# ZX_Distance_and_Gesture_Sensor_PTH.net
KiCad netlist of a schematic drawn in EAGLE
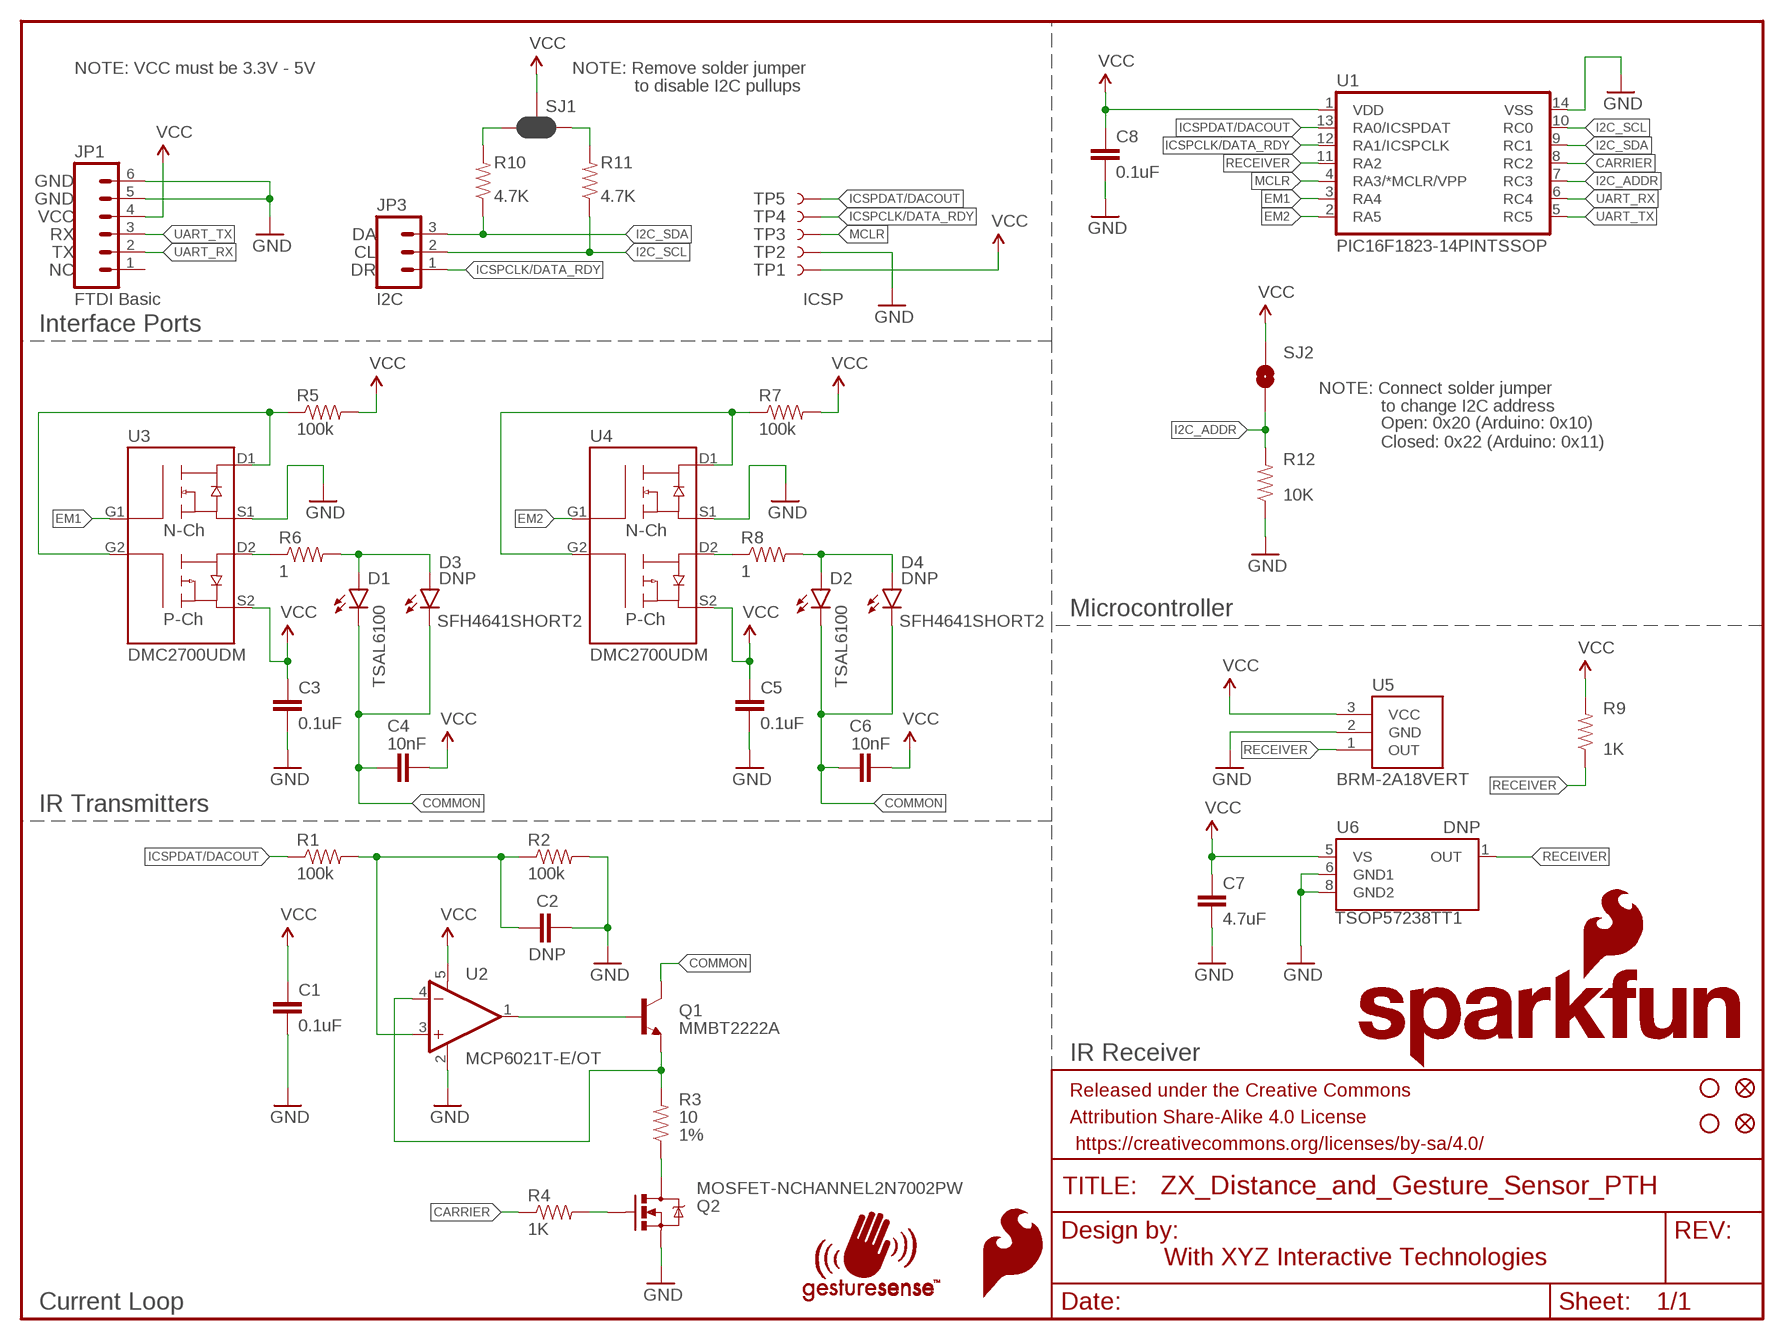
[diagram p0: schematic, sheet 1]

(export (version "E")
  (design (tool "Eeschema 10.0.6"))
  (components
    (comp (ref "C1")
      (value "0.1uF")
      (footprint "eagle-import:0603-CAP")
      (libsource (lib "eagle-import") (part "0.1UF-25V(+80/-20%)(0603)"))
    )
    (comp (ref "C2")
      (value "DNP")
      (footprint "eagle-import:0603-CAP")
      (libsource (lib "eagle-import") (part "CAP0603-CAP"))
    )
    (comp (ref "C3")
      (value "0.1uF")
      (footprint "eagle-import:0603-CAP")
      (libsource (lib "eagle-import") (part "0.1UF-25V(+80/-20%)(0603)"))
    )
    (comp (ref "C4")
      (value "10nF")
      (footprint "eagle-import:0603-CAP")
      (libsource (lib "eagle-import") (part "10NF/10000PF-50V-10%(0603)"))
    )
    (comp (ref "C5")
      (value "0.1uF")
      (footprint "eagle-import:0603-CAP")
      (libsource (lib "eagle-import") (part "0.1UF-25V(+80/-20%)(0603)"))
    )
    (comp (ref "C6")
      (value "10nF")
      (footprint "eagle-import:0603-CAP")
      (libsource (lib "eagle-import") (part "10NF/10000PF-50V-10%(0603)"))
    )
    (comp (ref "C7")
      (value "4.7uF")
      (footprint "eagle-import:0603-CAP")
      (libsource (lib "eagle-import") (part "4.7UF-6.3V-10%(0603)0603"))
    )
    (comp (ref "C8")
      (value "0.1uF")
      (footprint "eagle-import:0603-CAP")
      (libsource (lib "eagle-import") (part "0.1UF-25V(+80/-20%)(0603)"))
    )
    (comp (ref "D1")
      (value "LED-IR-THRUTSAL6100")
      (footprint "eagle-import:LED5MM")
      (fields (field (name "VARIANT") "TSAL6100"))
      (libsource (lib "eagle-import") (part "LED-IR-THRUTSAL6100"))
    )
    (comp (ref "D2")
      (value "LED-IR-THRUTSAL6100")
      (footprint "eagle-import:LED5MM")
      (fields (field (name "VARIANT") "TSAL6100"))
      (libsource (lib "eagle-import") (part "LED-IR-THRUTSAL6100"))
    )
    (comp (ref "D3")
      (value "SFH4641SHORT2")
      (footprint "eagle-import:SFH4641-SHORT2")
      (libsource (lib "eagle-import") (part "SFH4641SHORT2"))
    )
    (comp (ref "D4")
      (value "SFH4641SHORT2")
      (footprint "eagle-import:SFH4641-SHORT2")
      (libsource (lib "eagle-import") (part "SFH4641SHORT2"))
    )
    (comp (ref "FID1")
      (value "FIDUCIAL1X2")
      (footprint "eagle-import:FIDUCIAL-1X2")
      (libsource (lib "eagle-import") (part "FIDUCIAL1X2"))
    )
    (comp (ref "FID2")
      (value "FIDUCIAL1X2")
      (footprint "eagle-import:FIDUCIAL-1X2")
      (libsource (lib "eagle-import") (part "FIDUCIAL1X2"))
    )
    (comp (ref "FRAME1")
      (value "FRAME-LETTER")
      (footprint "eagle-import:CREATIVE_COMMONS")
      (libsource (lib "eagle-import") (part "FRAME-LETTER"))
    )
    (comp (ref "JP1")
      (value "M06NO_SILK_FEMALE_PTH")
      (footprint "eagle-import:1X06_NO_SILK")
      (libsource (lib "eagle-import") (part "M06NO_SILK_FEMALE_PTH"))
    )
    (comp (ref "JP3")
      (value "M031X03_NO_SILK")
      (footprint "eagle-import:1X03_NO_SILK")
      (libsource (lib "eagle-import") (part "M031X03_NO_SILK"))
    )
    (comp (ref "LOGO1")
      (value "SFE_LOGO_FLAME.1_INCH")
      (footprint "eagle-import:SFE_LOGO_FLAME_.1")
      (libsource (lib "eagle-import") (part "SFE_LOGO_FLAME.1_INCH"))
    )
    (comp (ref "Q1")
      (value "MMBT2222A")
      (footprint "eagle-import:SOT23-3")
      (libsource (lib "eagle-import") (part "TRANSISTOR_NPNMMBT2222A"))
    )
    (comp (ref "Q2")
      (value "MOSFET-NCHANNEL2N7002PW")
      (footprint "eagle-import:SOT323")
      (libsource (lib "eagle-import") (part "MOSFET-NCHANNEL2N7002PW"))
    )
    (comp (ref "R1")
      (value "100k")
      (footprint "eagle-import:0603-RES")
      (libsource (lib "eagle-import") (part "100KOHM-1/10W-1%(0603)"))
    )
    (comp (ref "R2")
      (value "100k")
      (footprint "eagle-import:0603-RES")
      (libsource (lib "eagle-import") (part "100KOHM-1/10W-1%(0603)"))
    )
    (comp (ref "R3")
      (value "10")
      (footprint "eagle-import:0603-RES")
      (fields (field (name "TOL") "1%"))
      (libsource (lib "eagle-import") (part "10OHM-1/10W-1%(0603)SMD"))
    )
    (comp (ref "R4")
      (value "1K")
      (footprint "eagle-import:0603-RES")
      (libsource (lib "eagle-import") (part "1KOHM-1/10W-1%(0603)"))
    )
    (comp (ref "R5")
      (value "100k")
      (footprint "eagle-import:0603-RES")
      (libsource (lib "eagle-import") (part "100KOHM-1/10W-1%(0603)"))
    )
    (comp (ref "R6")
      (value "1")
      (footprint "eagle-import:0603-RES")
      (libsource (lib "eagle-import") (part "1OHM1/10W1%(0603)"))
    )
    (comp (ref "R7")
      (value "100k")
      (footprint "eagle-import:0603-RES")
      (libsource (lib "eagle-import") (part "100KOHM-1/10W-1%(0603)"))
    )
    (comp (ref "R8")
      (value "1")
      (footprint "eagle-import:0603-RES")
      (libsource (lib "eagle-import") (part "1OHM1/10W1%(0603)"))
    )
    (comp (ref "R9")
      (value "1K")
      (footprint "eagle-import:0603-RES")
      (libsource (lib "eagle-import") (part "1KOHM-1/10W-1%(0603)"))
    )
    (comp (ref "R10")
      (value "4.7K")
      (footprint "eagle-import:0603-RES")
      (libsource (lib "eagle-import") (part "4.7KOHM-1/10W-1%(0603)"))
    )
    (comp (ref "R11")
      (value "4.7K")
      (footprint "eagle-import:0603-RES")
      (libsource (lib "eagle-import") (part "4.7KOHM-1/10W-1%(0603)"))
    )
    (comp (ref "R12")
      (value "10K")
      (footprint "eagle-import:0603-RES")
      (libsource (lib "eagle-import") (part "10KOHM-1/10W-1%(0603)0603"))
    )
    (comp (ref "SJ1")
      (value "JUMPER-PAD-3-NC_BY_PASTE")
      (footprint "eagle-import:PAD-JUMPER-3-NC_BY_PASTE_YES_SILK_FULL_BOX")
      (libsource (lib "eagle-import") (part "JUMPER-PAD-3-NC_BY_PASTE"))
    )
    (comp (ref "SJ2")
      (value "JUMPER-PAD-2-NOYES_SILK")
      (footprint "eagle-import:PAD-JUMPER-2-NO_YES_SILK")
      (libsource (lib "eagle-import") (part "JUMPER-PAD-2-NOYES_SILK"))
    )
    (comp (ref "STANDOFF1")
      (value "STAND-OFF")
      (footprint "eagle-import:STAND-OFF")
      (libsource (lib "eagle-import") (part "STAND-OFF"))
    )
    (comp (ref "STANDOFF2")
      (value "STAND-OFF")
      (footprint "eagle-import:STAND-OFF")
      (libsource (lib "eagle-import") (part "STAND-OFF"))
    )
    (comp (ref "TP1")
      (value "TEST-POINT3X4")
      (footprint "eagle-import:PAD.03X.04")
      (libsource (lib "eagle-import") (part "TEST-POINT3X4"))
    )
    (comp (ref "TP2")
      (value "TEST-POINT3X4")
      (footprint "eagle-import:PAD.03X.04")
      (libsource (lib "eagle-import") (part "TEST-POINT3X4"))
    )
    (comp (ref "TP3")
      (value "TEST-POINT3X4")
      (footprint "eagle-import:PAD.03X.04")
      (libsource (lib "eagle-import") (part "TEST-POINT3X4"))
    )
    (comp (ref "TP4")
      (value "TEST-POINT3X4")
      (footprint "eagle-import:PAD.03X.04")
      (libsource (lib "eagle-import") (part "TEST-POINT3X4"))
    )
    (comp (ref "TP5")
      (value "TEST-POINT3X4")
      (footprint "eagle-import:PAD.03X.04")
      (libsource (lib "eagle-import") (part "TEST-POINT3X4"))
    )
    (comp (ref "U$5")
      (value "SFE_LOGO_NAME_FLAME.1_INCH")
      (footprint "eagle-import:SFE_LOGO_NAME_FLAME_.1")
      (libsource (lib "eagle-import") (part "SFE_LOGO_NAME_FLAME.1_INCH"))
    )
    (comp (ref "U$6")
      (value "GESTURESENSE_LOGOSTEXT")
      (footprint "eagle-import:GESTURESENSE_TEXT")
      (libsource (lib "eagle-import") (part "GESTURESENSE_LOGOSTEXT"))
    )
    (comp (ref "U1")
      (value "PIC16F1823-14PINTSSOP")
      (footprint "eagle-import:TSSOP14")
      (libsource (lib "eagle-import") (part "PIC16F1823-14PINTSSOP"))
    )
    (comp (ref "U2")
      (value "MCP6021T-E/OT")
      (footprint "eagle-import:SOT23-5")
      (libsource (lib "eagle-import") (part "MCP6021T-E/OT"))
    )
    (comp (ref "U3")
      (value "DMC2700UDM")
      (footprint "eagle-import:SOT26")
      (libsource (lib "eagle-import") (part "DMC2700UDM"))
    )
    (comp (ref "U4")
      (value "DMC2700UDM")
      (footprint "eagle-import:SOT26")
      (libsource (lib "eagle-import") (part "DMC2700UDM"))
    )
    (comp (ref "U5")
      (value "BRM-2A18VERT")
      (footprint "eagle-import:BRM-2508_VERT")
      (libsource (lib "eagle-import") (part "BRM-2A18VERT"))
    )
    (comp (ref "U6")
      (value "TSOP57238TT1")
      (footprint "eagle-import:TSOP572")
      (fields (field (name "PLACE") "DNP"))
      (libsource (lib "eagle-import") (part "TSOP57238TT1"))
    )
  )
  (nets
    (net (code "1") (name "CARRIER") (class "Default")
      (node (ref "R4") (pin "1") (pinfunction "1_1") (pintype "passive"))
      (node (ref "U1") (pin "8") (pinfunction "RC2_8") (pintype "bidirectional"))
    )
    (net (code "2") (name "COMMON") (class "Default")
      (node (ref "C4") (pin "1") (pinfunction "1_1") (pintype "passive"))
      (node (ref "C6") (pin "1") (pinfunction "1_1") (pintype "passive"))
      (node (ref "D1") (pin "K") (pinfunction "C_K") (pintype "passive"))
      (node (ref "D2") (pin "K") (pinfunction "C_K") (pintype "passive"))
      (node (ref "D3") (pin "C") (pinfunction "C_C") (pintype "passive"))
      (node (ref "D4") (pin "C") (pinfunction "C_C") (pintype "passive"))
      (node (ref "Q1") (pin "3") (pinfunction "C_3") (pintype "passive"))
    )
    (net (code "3") (name "EM1") (class "Default")
      (node (ref "U1") (pin "3") (pinfunction "RA4_3") (pintype "bidirectional"))
      (node (ref "U3") (pin "G1") (pinfunction "G1_G1") (pintype "bidirectional"))
    )
    (net (code "4") (name "EM2") (class "Default")
      (node (ref "U1") (pin "2") (pinfunction "RA5_2") (pintype "bidirectional"))
      (node (ref "U4") (pin "G1") (pinfunction "G1_G1") (pintype "bidirectional"))
    )
    (net (code "5") (name "GND") (class "Default")
      (node (ref "C1") (pin "2") (pinfunction "2_2") (pintype "passive"))
      (node (ref "C2") (pin "2") (pinfunction "2_2") (pintype "passive"))
      (node (ref "C3") (pin "2") (pinfunction "2_2") (pintype "passive"))
      (node (ref "C5") (pin "2") (pinfunction "2_2") (pintype "passive"))
      (node (ref "C7") (pin "2") (pinfunction "2_2") (pintype "passive"))
      (node (ref "C8") (pin "2") (pinfunction "2_2") (pintype "passive"))
      (node (ref "JP1") (pin "5") (pinfunction "5_5") (pintype "passive"))
      (node (ref "JP1") (pin "6") (pinfunction "6_6") (pintype "passive"))
      (node (ref "Q2") (pin "2") (pinfunction "S_2") (pintype "passive"))
      (node (ref "R12") (pin "1") (pinfunction "1_1") (pintype "passive"))
      (node (ref "R2") (pin "2") (pinfunction "2_2") (pintype "passive"))
      (node (ref "TP2") (pin "P$1") (pinfunction "1_P$1") (pintype "bidirectional"))
      (node (ref "U1") (pin "14") (pinfunction "VSS_14") (pintype "power_in"))
      (node (ref "U2") (pin "2") (pinfunction "V-_2") (pintype "power_in"))
      (node (ref "U3") (pin "S1") (pinfunction "S1_S1") (pintype "bidirectional"))
      (node (ref "U4") (pin "S1") (pinfunction "S1_S1") (pintype "bidirectional"))
      (node (ref "U5") (pin "2") (pinfunction "GND_2") (pintype "bidirectional"))
      (node (ref "U6") (pin "6") (pinfunction "GND1_6") (pintype "bidirectional"))
      (node (ref "U6") (pin "8") (pinfunction "GND2_8") (pintype "bidirectional"))
    )
    (net (code "6") (name "I2C_ADDR") (class "Default")
      (node (ref "R12") (pin "2") (pinfunction "2_2") (pintype "passive"))
      (node (ref "SJ2") (pin "1") (pinfunction "1_1") (pintype "passive"))
      (node (ref "U1") (pin "7") (pinfunction "RC3_7") (pintype "bidirectional"))
    )
    (net (code "7") (name "I2C_SCL") (class "Default")
      (node (ref "JP3") (pin "2") (pinfunction "2_2") (pintype "passive"))
      (node (ref "R11") (pin "1") (pinfunction "1_1") (pintype "passive"))
      (node (ref "U1") (pin "10") (pinfunction "RC0_10") (pintype "bidirectional"))
    )
    (net (code "8") (name "I2C_SDA") (class "Default")
      (node (ref "JP3") (pin "3") (pinfunction "3_3") (pintype "passive"))
      (node (ref "R10") (pin "1") (pinfunction "1_1") (pintype "passive"))
      (node (ref "U1") (pin "9") (pinfunction "RC1_9") (pintype "bidirectional"))
    )
    (net (code "9") (name "ICSPCLK{slash}DATA_RDY") (class "Default")
      (node (ref "JP3") (pin "1") (pinfunction "1_1") (pintype "passive"))
      (node (ref "TP4") (pin "P$1") (pinfunction "1_P$1") (pintype "bidirectional"))
      (node (ref "U1") (pin "12") (pinfunction "RA1/ICSPCLK_12") (pintype "bidirectional"))
    )
    (net (code "10") (name "ICSPDAT{slash}DACOUT") (class "Default")
      (node (ref "R1") (pin "1") (pinfunction "1_1") (pintype "passive"))
      (node (ref "TP5") (pin "P$1") (pinfunction "1_P$1") (pintype "bidirectional"))
      (node (ref "U1") (pin "13") (pinfunction "RA0/ICSPDAT_13") (pintype "bidirectional"))
    )
    (net (code "11") (name "MCLR") (class "Default")
      (node (ref "TP3") (pin "P$1") (pinfunction "1_P$1") (pintype "bidirectional"))
      (node (ref "U1") (pin "4") (pinfunction "RA3/*MCLR/VPP_4") (pintype "input"))
    )
    (net (code "12") (name "Net-(D1-PadA)") (class "Default")
      (node (ref "D1") (pin "A") (pinfunction "A_A") (pintype "passive"))
      (node (ref "D3") (pin "A") (pinfunction "A_A") (pintype "passive"))
      (node (ref "R6") (pin "2") (pinfunction "2_2") (pintype "passive"))
    )
    (net (code "13") (name "Net-(D2-PadA)") (class "Default")
      (node (ref "D2") (pin "A") (pinfunction "A_A") (pintype "passive"))
      (node (ref "D4") (pin "A") (pinfunction "A_A") (pintype "passive"))
      (node (ref "R8") (pin "2") (pinfunction "2_2") (pintype "passive"))
    )
    (net (code "14") (name "Net-(Q1-B)") (class "Default")
      (node (ref "Q1") (pin "1") (pinfunction "B_1") (pintype "passive"))
      (node (ref "U2") (pin "1") (pinfunction "OUT_1") (pintype "output"))
    )
    (net (code "15") (name "Net-(Q1-E)") (class "Default")
      (node (ref "Q1") (pin "2") (pinfunction "E_2") (pintype "passive"))
      (node (ref "R3") (pin "2") (pinfunction "2_2") (pintype "passive"))
      (node (ref "U2") (pin "4") (pinfunction "-IN_4") (pintype "input"))
    )
    (net (code "16") (name "Net-(Q2-D)") (class "Default")
      (node (ref "Q2") (pin "3") (pinfunction "D_3") (pintype "passive"))
      (node (ref "R3") (pin "1") (pinfunction "1_1") (pintype "passive"))
    )
    (net (code "17") (name "Net-(Q2-G)") (class "Default")
      (node (ref "Q2") (pin "1") (pinfunction "G_1") (pintype "passive"))
      (node (ref "R4") (pin "2") (pinfunction "2_2") (pintype "passive"))
    )
    (net (code "18") (name "Net-(R5-Pad1)") (class "Default")
      (node (ref "R5") (pin "1") (pinfunction "1_1") (pintype "passive"))
      (node (ref "U3") (pin "D1") (pinfunction "D1_D1") (pintype "bidirectional"))
      (node (ref "U3") (pin "G2") (pinfunction "G2_G2") (pintype "bidirectional"))
    )
    (net (code "19") (name "Net-(R6-Pad1)") (class "Default")
      (node (ref "R6") (pin "1") (pinfunction "1_1") (pintype "passive"))
      (node (ref "U3") (pin "D2") (pinfunction "D2_D2") (pintype "bidirectional"))
    )
    (net (code "20") (name "Net-(R7-Pad1)") (class "Default")
      (node (ref "R7") (pin "1") (pinfunction "1_1") (pintype "passive"))
      (node (ref "U4") (pin "D1") (pinfunction "D1_D1") (pintype "bidirectional"))
      (node (ref "U4") (pin "G2") (pinfunction "G2_G2") (pintype "bidirectional"))
    )
    (net (code "21") (name "Net-(R8-Pad1)") (class "Default")
      (node (ref "R8") (pin "1") (pinfunction "1_1") (pintype "passive"))
      (node (ref "U4") (pin "D2") (pinfunction "D2_D2") (pintype "bidirectional"))
    )
    (net (code "22") (name "Net-(R10-Pad2)") (class "Default")
      (node (ref "R10") (pin "2") (pinfunction "2_2") (pintype "passive"))
      (node (ref "SJ1") (pin "3") (pinfunction "3_3") (pintype "passive"))
    )
    (net (code "23") (name "Net-(R11-Pad2)") (class "Default")
      (node (ref "R11") (pin "2") (pinfunction "2_2") (pintype "passive"))
      (node (ref "SJ1") (pin "1") (pinfunction "1_1") (pintype "passive"))
    )
    (net (code "24") (name "Net-(U2-+IN)") (class "Default")
      (node (ref "C2") (pin "1") (pinfunction "1_1") (pintype "passive"))
      (node (ref "R1") (pin "2") (pinfunction "2_2") (pintype "passive"))
      (node (ref "R2") (pin "1") (pinfunction "1_1") (pintype "passive"))
      (node (ref "U2") (pin "3") (pinfunction "+IN_3") (pintype "input"))
    )
    (net (code "25") (name "RECEIVER") (class "Default")
      (node (ref "R9") (pin "1") (pinfunction "1_1") (pintype "passive"))
      (node (ref "U1") (pin "11") (pinfunction "RA2_11") (pintype "bidirectional"))
      (node (ref "U5") (pin "1") (pinfunction "OUT_1") (pintype "bidirectional"))
      (node (ref "U6") (pin "1") (pinfunction "OUT_1") (pintype "bidirectional"))
    )
    (net (code "26") (name "UART_RX") (class "Default")
      (node (ref "JP1") (pin "2") (pinfunction "2_2") (pintype "passive"))
      (node (ref "U1") (pin "6") (pinfunction "RC4_6") (pintype "bidirectional"))
    )
    (net (code "27") (name "UART_TX") (class "Default")
      (node (ref "JP1") (pin "3") (pinfunction "3_3") (pintype "passive"))
      (node (ref "U1") (pin "5") (pinfunction "RC5_5") (pintype "bidirectional"))
    )
    (net (code "28") (name "VCC") (class "Default")
      (node (ref "C1") (pin "1") (pinfunction "1_1") (pintype "passive"))
      (node (ref "C3") (pin "1") (pinfunction "1_1") (pintype "passive"))
      (node (ref "C4") (pin "2") (pinfunction "2_2") (pintype "passive"))
      (node (ref "C5") (pin "1") (pinfunction "1_1") (pintype "passive"))
      (node (ref "C6") (pin "2") (pinfunction "2_2") (pintype "passive"))
      (node (ref "C7") (pin "1") (pinfunction "1_1") (pintype "passive"))
      (node (ref "C8") (pin "1") (pinfunction "1_1") (pintype "passive"))
      (node (ref "JP1") (pin "4") (pinfunction "4_4") (pintype "passive"))
      (node (ref "R5") (pin "2") (pinfunction "2_2") (pintype "passive"))
      (node (ref "R7") (pin "2") (pinfunction "2_2") (pintype "passive"))
      (node (ref "R9") (pin "2") (pinfunction "2_2") (pintype "passive"))
      (node (ref "SJ1") (pin "2") (pinfunction "2_2") (pintype "passive"))
      (node (ref "SJ2") (pin "2") (pinfunction "2_2") (pintype "passive"))
      (node (ref "TP1") (pin "P$1") (pinfunction "1_P$1") (pintype "bidirectional"))
      (node (ref "U1") (pin "1") (pinfunction "VDD_1") (pintype "power_in"))
      (node (ref "U2") (pin "5") (pinfunction "V+_5") (pintype "power_in"))
      (node (ref "U3") (pin "S2") (pinfunction "S2_S2") (pintype "bidirectional"))
      (node (ref "U4") (pin "S2") (pinfunction "S2_S2") (pintype "bidirectional"))
      (node (ref "U5") (pin "3") (pinfunction "VCC_3") (pintype "bidirectional"))
      (node (ref "U6") (pin "5") (pinfunction "VS_5") (pintype "bidirectional"))
    )
    (net (code "29") (name "unconnected-(JP1-Pad1)") (class "Default")
      (node (ref "JP1") (pin "1") (pinfunction "1_1") (pintype "passive"))
    )
  )
)
